# Secon2014_final_Schematic.net
KiCad netlist of a schematic drawn in EAGLE
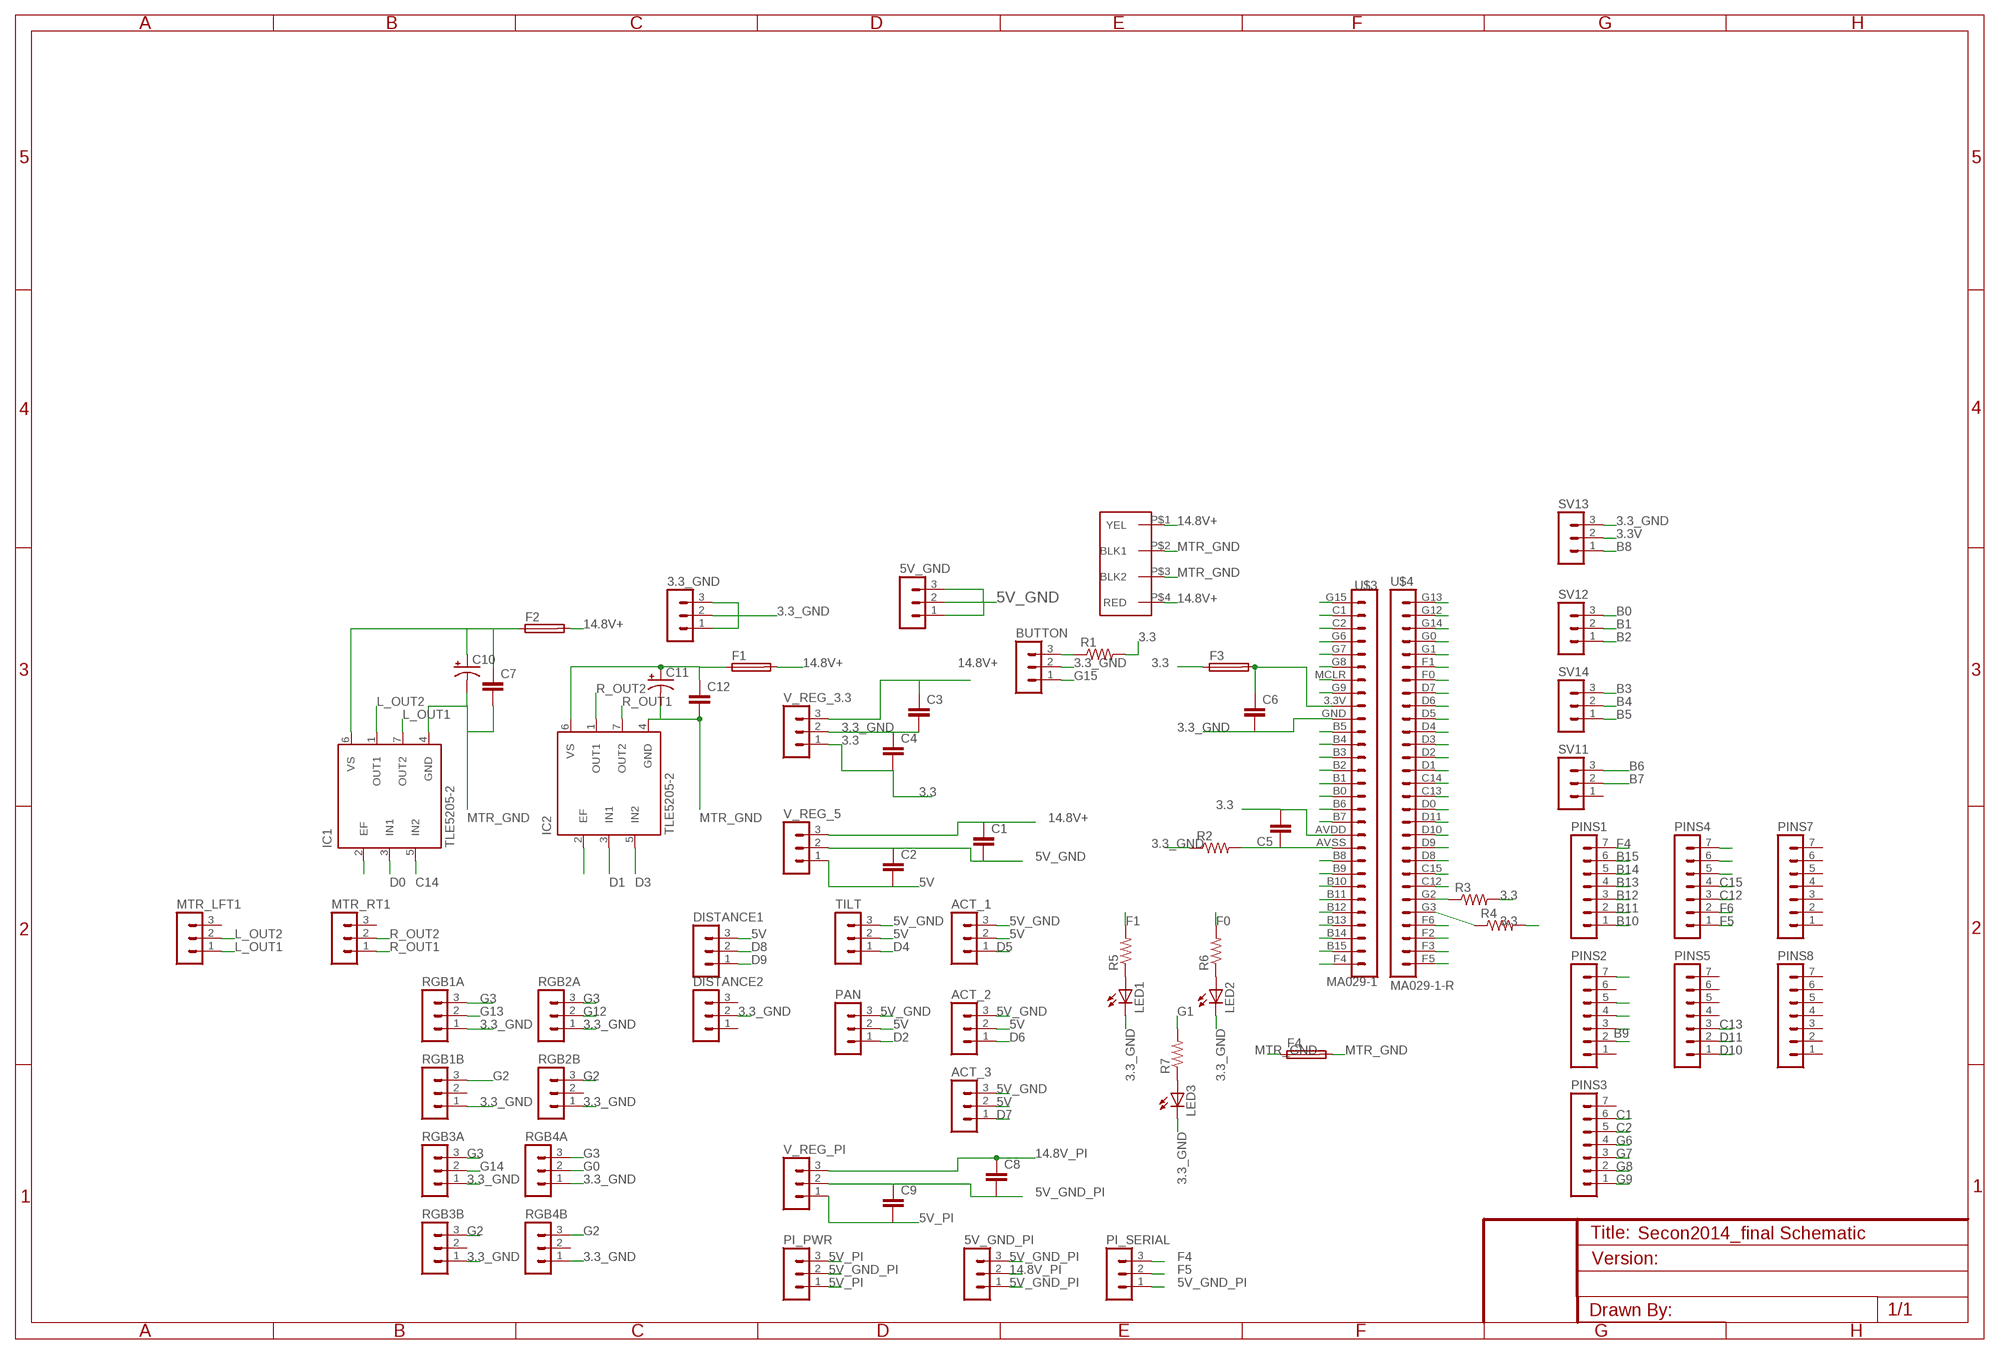
[diagram p0: schematic, sheet 1]

(export (version "E")
  (design (tool "Eeschema 10.0.6"))
  (components
    (comp (ref "3.3_GND")
      (value "MA03-1")
      (footprint "eagle-import:MA03-1")
      (libsource (lib "eagle-import") (part "MA03-1"))
    )
    (comp (ref "5V_GND")
      (value "MA03-1")
      (footprint "eagle-import:MA03-1")
      (libsource (lib "eagle-import") (part "MA03-1"))
    )
    (comp (ref "5V_GND_PI")
      (value "MA03-1")
      (footprint "eagle-import:MA03-1")
      (libsource (lib "eagle-import") (part "MA03-1"))
    )
    (comp (ref "ACT_1")
      (value "MA03-1")
      (footprint "eagle-import:MA03-1")
      (libsource (lib "eagle-import") (part "MA03-1"))
    )
    (comp (ref "ACT_2")
      (value "MA03-1")
      (footprint "eagle-import:MA03-1")
      (libsource (lib "eagle-import") (part "MA03-1"))
    )
    (comp (ref "ACT_3")
      (value "MA03-1")
      (footprint "eagle-import:MA03-1")
      (fields (field (name "OC_FARNELL") "unknown") (field (name "OC_NEWARK") "unknown"))
      (libsource (lib "eagle-import") (part "MA03-1"))
    )
    (comp (ref "BUTTON")
      (value "MA03-1")
      (footprint "eagle-import:MA03-1")
      (fields (field (name "OC_FARNELL") "unknown") (field (name "OC_NEWARK") "unknown"))
      (libsource (lib "eagle-import") (part "MA03-1"))
    )
    (comp (ref "C1")
      (value "CAPPTH2")
      (footprint "eagle-import:CAP-PTH-SMALL2")
      (libsource (lib "eagle-import") (part "CAPPTH2"))
    )
    (comp (ref "C2")
      (value "CAPPTH2")
      (footprint "eagle-import:CAP-PTH-SMALL2")
      (libsource (lib "eagle-import") (part "CAPPTH2"))
    )
    (comp (ref "C3")
      (value "CAPPTH2")
      (footprint "eagle-import:CAP-PTH-SMALL2")
      (libsource (lib "eagle-import") (part "CAPPTH2"))
    )
    (comp (ref "C4")
      (value "CAPPTH2")
      (footprint "eagle-import:CAP-PTH-SMALL2")
      (libsource (lib "eagle-import") (part "CAPPTH2"))
    )
    (comp (ref "C5")
      (value "CAPPTH2")
      (footprint "eagle-import:CAP-PTH-SMALL2")
      (libsource (lib "eagle-import") (part "CAPPTH2"))
    )
    (comp (ref "C6")
      (value "CAPPTH2")
      (footprint "eagle-import:CAP-PTH-SMALL2")
      (libsource (lib "eagle-import") (part "CAPPTH2"))
    )
    (comp (ref "C7")
      (value "CAPPTH2")
      (footprint "eagle-import:CAP-PTH-SMALL2")
      (libsource (lib "eagle-import") (part "CAPPTH2"))
    )
    (comp (ref "C8")
      (value "CAPPTH2")
      (footprint "eagle-import:CAP-PTH-SMALL2")
      (libsource (lib "eagle-import") (part "CAPPTH2"))
    )
    (comp (ref "C9")
      (value "CAPPTH2")
      (footprint "eagle-import:CAP-PTH-SMALL2")
      (libsource (lib "eagle-import") (part "CAPPTH2"))
    )
    (comp (ref "C10")
      (value "CAP_POLPTH1")
      (footprint "eagle-import:CPOL-RADIAL-100UF-25V")
      (libsource (lib "eagle-import") (part "CAP_POLPTH1"))
    )
    (comp (ref "C11")
      (value "CAP_POLPTH1")
      (footprint "eagle-import:CPOL-RADIAL-100UF-25V")
      (libsource (lib "eagle-import") (part "CAP_POLPTH1"))
    )
    (comp (ref "C12")
      (value "CAPPTH2")
      (footprint "eagle-import:CAP-PTH-SMALL2")
      (libsource (lib "eagle-import") (part "CAPPTH2"))
    )
    (comp (ref "DISTANCE1")
      (value "MA03-1")
      (footprint "eagle-import:MA03-1")
      (libsource (lib "eagle-import") (part "MA03-1"))
    )
    (comp (ref "DISTANCE2")
      (value "MA03-1")
      (footprint "eagle-import:MA03-1")
      (libsource (lib "eagle-import") (part "MA03-1"))
    )
    (comp (ref "F1")
      (value "TE5")
      (footprint "eagle-import:TE5")
      (libsource (lib "eagle-import") (part "TE5"))
    )
    (comp (ref "F2")
      (value "TE5")
      (footprint "eagle-import:TE5")
      (libsource (lib "eagle-import") (part "TE5"))
    )
    (comp (ref "F3")
      (value "TE5")
      (footprint "eagle-import:TE5")
      (libsource (lib "eagle-import") (part "TE5"))
    )
    (comp (ref "F4")
      (value "TE5")
      (footprint "eagle-import:TE5")
      (fields (field (name "OC_FARNELL") "unknown") (field (name "OC_NEWARK") "unknown"))
      (libsource (lib "eagle-import") (part "TE5"))
    )
    (comp (ref "IC1")
      (value "TLE5205-2")
      (footprint "eagle-import:P-TO220-7-11")
      (libsource (lib "eagle-import") (part "TLE5205-2"))
    )
    (comp (ref "IC2")
      (value "TLE5205-2")
      (footprint "eagle-import:P-TO220-7-11")
      (libsource (lib "eagle-import") (part "TLE5205-2"))
    )
    (comp (ref "LED1")
      (value "LED5MM")
      (footprint "eagle-import:LED5MM")
      (libsource (lib "eagle-import") (part "LED5MM"))
    )
    (comp (ref "LED2")
      (value "LED5MM")
      (footprint "eagle-import:LED5MM")
      (libsource (lib "eagle-import") (part "LED5MM"))
    )
    (comp (ref "LED3")
      (value "LED5MM")
      (footprint "eagle-import:LED5MM")
      (libsource (lib "eagle-import") (part "LED5MM"))
    )
    (comp (ref "MTR_LFT1")
      (value "MA03-1")
      (footprint "eagle-import:MA03-1")
      (libsource (lib "eagle-import") (part "MA03-1"))
    )
    (comp (ref "MTR_RT1")
      (value "MA03-1")
      (footprint "eagle-import:MA03-1")
      (libsource (lib "eagle-import") (part "MA03-1"))
    )
    (comp (ref "PAN")
      (value "MA03-1")
      (footprint "eagle-import:MA03-1")
      (libsource (lib "eagle-import") (part "MA03-1"))
    )
    (comp (ref "PINS1")
      (value "MA07-1")
      (footprint "eagle-import:MA07-1")
      (libsource (lib "eagle-import") (part "MA07-1"))
    )
    (comp (ref "PINS2")
      (value "MA07-1")
      (footprint "eagle-import:MA07-1")
      (libsource (lib "eagle-import") (part "MA07-1"))
    )
    (comp (ref "PINS3")
      (value "MA07-1")
      (footprint "eagle-import:MA07-1")
      (libsource (lib "eagle-import") (part "MA07-1"))
    )
    (comp (ref "PINS4")
      (value "MA07-1")
      (footprint "eagle-import:MA07-1")
      (libsource (lib "eagle-import") (part "MA07-1"))
    )
    (comp (ref "PINS5")
      (value "MA07-1")
      (footprint "eagle-import:MA07-1")
      (libsource (lib "eagle-import") (part "MA07-1"))
    )
    (comp (ref "PINS7")
      (value "MA07-1")
      (footprint "eagle-import:MA07-1")
      (libsource (lib "eagle-import") (part "MA07-1"))
    )
    (comp (ref "PINS8")
      (value "MA07-1")
      (footprint "eagle-import:MA07-1")
      (libsource (lib "eagle-import") (part "MA07-1"))
    )
    (comp (ref "PI_PWR")
      (value "MA03-1")
      (footprint "eagle-import:MA03-1")
      (libsource (lib "eagle-import") (part "MA03-1"))
    )
    (comp (ref "PI_SERIAL")
      (value "MA03-1")
      (footprint "eagle-import:MA03-1")
      (fields (field (name "OC_FARNELL") "unknown") (field (name "OC_NEWARK") "unknown"))
      (libsource (lib "eagle-import") (part "MA03-1"))
    )
    (comp (ref "R1")
      (value "RESISTORPTH-1/4W")
      (footprint "eagle-import:AXIAL-0.4")
      (libsource (lib "eagle-import") (part "RESISTORPTH-1/4W"))
    )
    (comp (ref "R2")
      (value "RESISTORPTH-1/4W")
      (footprint "eagle-import:AXIAL-0.4")
      (libsource (lib "eagle-import") (part "RESISTORPTH-1/4W"))
    )
    (comp (ref "R3")
      (value "RESISTORPTH-1/4W")
      (footprint "eagle-import:AXIAL-0.4")
      (libsource (lib "eagle-import") (part "RESISTORPTH-1/4W"))
    )
    (comp (ref "R4")
      (value "RESISTORPTH-1/4W")
      (footprint "eagle-import:AXIAL-0.4")
      (libsource (lib "eagle-import") (part "RESISTORPTH-1/4W"))
    )
    (comp (ref "R5")
      (value "RESISTORPTH-1/4W")
      (footprint "eagle-import:AXIAL-0.4")
      (libsource (lib "eagle-import") (part "RESISTORPTH-1/4W"))
    )
    (comp (ref "R6")
      (value "RESISTORPTH-1/4W")
      (footprint "eagle-import:AXIAL-0.4")
      (libsource (lib "eagle-import") (part "RESISTORPTH-1/4W"))
    )
    (comp (ref "R7")
      (value "RESISTORPTH-1/4W")
      (footprint "eagle-import:AXIAL-0.4")
      (libsource (lib "eagle-import") (part "RESISTORPTH-1/4W"))
    )
    (comp (ref "RGB1A")
      (value "MA03-1")
      (footprint "eagle-import:MA03-1")
      (libsource (lib "eagle-import") (part "MA03-1"))
    )
    (comp (ref "RGB1B")
      (value "MA03-1")
      (footprint "eagle-import:MA03-1")
      (libsource (lib "eagle-import") (part "MA03-1"))
    )
    (comp (ref "RGB2A")
      (value "MA03-1")
      (footprint "eagle-import:MA03-1")
      (libsource (lib "eagle-import") (part "MA03-1"))
    )
    (comp (ref "RGB2B")
      (value "MA03-1")
      (footprint "eagle-import:MA03-1")
      (libsource (lib "eagle-import") (part "MA03-1"))
    )
    (comp (ref "RGB3A")
      (value "MA03-1")
      (footprint "eagle-import:MA03-1")
      (libsource (lib "eagle-import") (part "MA03-1"))
    )
    (comp (ref "RGB3B")
      (value "MA03-1")
      (footprint "eagle-import:MA03-1")
      (libsource (lib "eagle-import") (part "MA03-1"))
    )
    (comp (ref "RGB4A")
      (value "MA03-1")
      (footprint "eagle-import:MA03-1")
      (libsource (lib "eagle-import") (part "MA03-1"))
    )
    (comp (ref "RGB4B")
      (value "MA03-1")
      (footprint "eagle-import:MA03-1")
      (libsource (lib "eagle-import") (part "MA03-1"))
    )
    (comp (ref "SV11")
      (value "MA03-1")
      (footprint "eagle-import:MA03-1")
      (libsource (lib "eagle-import") (part "MA03-1"))
    )
    (comp (ref "SV12")
      (value "MA03-1")
      (footprint "eagle-import:MA03-1")
      (libsource (lib "eagle-import") (part "MA03-1"))
    )
    (comp (ref "SV13")
      (value "MA03-1")
      (footprint "eagle-import:MA03-1")
      (libsource (lib "eagle-import") (part "MA03-1"))
    )
    (comp (ref "SV14")
      (value "MA03-1")
      (footprint "eagle-import:MA03-1")
      (libsource (lib "eagle-import") (part "MA03-1"))
    )
    (comp (ref "TILT")
      (value "MA03-1")
      (footprint "eagle-import:MA03-1")
      (libsource (lib "eagle-import") (part "MA03-1"))
    )
    (comp (ref "U$1")
      (value "MOLEX-4PINPWR")
      (footprint "eagle-import:MOLEX_4PWR")
      (libsource (lib "eagle-import") (part "MOLEX-4PINPWR"))
    )
    (comp (ref "U$3")
      (value "MA029-1")
      (footprint "eagle-import:MA029-1")
      (libsource (lib "eagle-import") (part "MA029-1"))
    )
    (comp (ref "U$4")
      (value "MA029-1-R")
      (footprint "eagle-import:MA029-1-R")
      (libsource (lib "eagle-import") (part "MA029-1-R"))
    )
    (comp (ref "V_REG_3.3")
      (value "MA03-1")
      (footprint "eagle-import:MA03-1")
      (libsource (lib "eagle-import") (part "MA03-1"))
    )
    (comp (ref "V_REG_5")
      (value "MA03-1")
      (footprint "eagle-import:MA03-1")
      (libsource (lib "eagle-import") (part "MA03-1"))
    )
    (comp (ref "V_REG_PI")
      (value "MA03-1")
      (footprint "eagle-import:MA03-1")
      (libsource (lib "eagle-import") (part "MA03-1"))
    )
  )
  (nets
    (net (code "1") (name "/3.3") (class "Default")
      (node (ref "C4") (pin "2") (pinfunction "2_2") (pintype "passive"))
      (node (ref "C5") (pin "2") (pinfunction "2_2") (pintype "passive"))
      (node (ref "F3") (pin "1") (pinfunction "1_1") (pintype "passive"))
      (node (ref "R1") (pin "P$2") (pinfunction "2_P$2") (pintype "passive"))
      (node (ref "R3") (pin "P$2") (pinfunction "2_P$2") (pintype "passive"))
      (node (ref "R4") (pin "P$2") (pinfunction "2_P$2") (pintype "passive"))
      (node (ref "U$3") (pin "AVDD") (pinfunction "19_AVDD") (pintype "passive"))
      (node (ref "V_REG_3.3") (pin "1") (pinfunction "1_1") (pintype "passive"))
    )
    (net (code "2") (name "/3.3V") (class "Default")
      (node (ref "SV13") (pin "2") (pinfunction "2_2") (pintype "passive"))
    )
    (net (code "3") (name "/3.3_GND") (class "Default")
      (node (ref "3.3_GND") (pin "1") (pinfunction "1_1") (pintype "passive"))
      (node (ref "3.3_GND") (pin "2") (pinfunction "2_2") (pintype "passive"))
      (node (ref "3.3_GND") (pin "3") (pinfunction "3_3") (pintype "passive"))
      (node (ref "BUTTON") (pin "2") (pinfunction "2_2") (pintype "passive"))
      (node (ref "C3") (pin "2") (pinfunction "2_2") (pintype "passive"))
      (node (ref "C4") (pin "1") (pinfunction "1_1") (pintype "passive"))
      (node (ref "C6") (pin "2") (pinfunction "2_2") (pintype "passive"))
      (node (ref "DISTANCE2") (pin "2") (pinfunction "2_2") (pintype "passive"))
      (node (ref "LED1") (pin "K") (pinfunction "C_K") (pintype "passive"))
      (node (ref "LED2") (pin "K") (pinfunction "C_K") (pintype "passive"))
      (node (ref "LED3") (pin "K") (pinfunction "C_K") (pintype "passive"))
      (node (ref "R2") (pin "P$1") (pinfunction "1_P$1") (pintype "passive"))
      (node (ref "RGB1A") (pin "1") (pinfunction "1_1") (pintype "passive"))
      (node (ref "RGB1B") (pin "1") (pinfunction "1_1") (pintype "passive"))
      (node (ref "RGB2A") (pin "1") (pinfunction "1_1") (pintype "passive"))
      (node (ref "RGB2B") (pin "1") (pinfunction "1_1") (pintype "passive"))
      (node (ref "RGB3A") (pin "1") (pinfunction "1_1") (pintype "passive"))
      (node (ref "RGB3B") (pin "1") (pinfunction "1_1") (pintype "passive"))
      (node (ref "RGB4A") (pin "1") (pinfunction "1_1") (pintype "passive"))
      (node (ref "RGB4B") (pin "1") (pinfunction "1_1") (pintype "passive"))
      (node (ref "SV13") (pin "3") (pinfunction "3_3") (pintype "passive"))
      (node (ref "U$3") (pin "GND") (pinfunction "10_GND") (pintype "passive"))
      (node (ref "V_REG_3.3") (pin "2") (pinfunction "2_2") (pintype "passive"))
    )
    (net (code "4") (name "/5V") (class "Default")
      (node (ref "ACT_1") (pin "2") (pinfunction "2_2") (pintype "passive"))
      (node (ref "ACT_2") (pin "2") (pinfunction "2_2") (pintype "passive"))
      (node (ref "ACT_3") (pin "2") (pinfunction "2_2") (pintype "passive"))
      (node (ref "C2") (pin "2") (pinfunction "2_2") (pintype "passive"))
      (node (ref "DISTANCE1") (pin "3") (pinfunction "3_3") (pintype "passive"))
      (node (ref "PAN") (pin "2") (pinfunction "2_2") (pintype "passive"))
      (node (ref "TILT") (pin "2") (pinfunction "2_2") (pintype "passive"))
      (node (ref "V_REG_5") (pin "1") (pinfunction "1_1") (pintype "passive"))
    )
    (net (code "5") (name "/5V_GND") (class "Default")
      (node (ref "5V_GND") (pin "1") (pinfunction "1_1") (pintype "passive"))
      (node (ref "5V_GND") (pin "2") (pinfunction "2_2") (pintype "passive"))
      (node (ref "5V_GND") (pin "3") (pinfunction "3_3") (pintype "passive"))
      (node (ref "ACT_1") (pin "3") (pinfunction "3_3") (pintype "passive"))
      (node (ref "ACT_2") (pin "3") (pinfunction "3_3") (pintype "passive"))
      (node (ref "ACT_3") (pin "3") (pinfunction "3_3") (pintype "passive"))
      (node (ref "C1") (pin "2") (pinfunction "2_2") (pintype "passive"))
      (node (ref "C2") (pin "1") (pinfunction "1_1") (pintype "passive"))
      (node (ref "PAN") (pin "3") (pinfunction "3_3") (pintype "passive"))
      (node (ref "TILT") (pin "3") (pinfunction "3_3") (pintype "passive"))
      (node (ref "V_REG_5") (pin "2") (pinfunction "2_2") (pintype "passive"))
    )
    (net (code "6") (name "/5V_GND_PI") (class "Default")
      (node (ref "5V_GND_PI") (pin "1") (pinfunction "1_1") (pintype "passive"))
      (node (ref "5V_GND_PI") (pin "3") (pinfunction "3_3") (pintype "passive"))
      (node (ref "C8") (pin "2") (pinfunction "2_2") (pintype "passive"))
      (node (ref "C9") (pin "1") (pinfunction "1_1") (pintype "passive"))
      (node (ref "PI_PWR") (pin "2") (pinfunction "2_2") (pintype "passive"))
      (node (ref "PI_SERIAL") (pin "1") (pinfunction "1_1") (pintype "passive"))
      (node (ref "V_REG_PI") (pin "2") (pinfunction "2_2") (pintype "passive"))
    )
    (net (code "7") (name "/5V_PI") (class "Default")
      (node (ref "C9") (pin "2") (pinfunction "2_2") (pintype "passive"))
      (node (ref "PI_PWR") (pin "1") (pinfunction "1_1") (pintype "passive"))
      (node (ref "PI_PWR") (pin "3") (pinfunction "3_3") (pintype "passive"))
      (node (ref "V_REG_PI") (pin "1") (pinfunction "1_1") (pintype "passive"))
    )
    (net (code "8") (name "/14.8V+") (class "Default")
      (node (ref "C1") (pin "1") (pinfunction "1_1") (pintype "passive"))
      (node (ref "C3") (pin "1") (pinfunction "1_1") (pintype "passive"))
      (node (ref "F1") (pin "2") (pinfunction "2_2") (pintype "passive"))
      (node (ref "F2") (pin "2") (pinfunction "2_2") (pintype "passive"))
      (node (ref "U$1") (pin "P$1") (pinfunction "YEL_P$1") (pintype "bidirectional"))
      (node (ref "U$1") (pin "P$4") (pinfunction "RED_P$4") (pintype "bidirectional"))
      (node (ref "V_REG_3.3") (pin "3") (pinfunction "3_3") (pintype "passive"))
      (node (ref "V_REG_5") (pin "3") (pinfunction "3_3") (pintype "passive"))
    )
    (net (code "9") (name "/14.8V_PI") (class "Default")
      (node (ref "5V_GND_PI") (pin "2") (pinfunction "2_2") (pintype "passive"))
      (node (ref "C8") (pin "1") (pinfunction "1_1") (pintype "passive"))
      (node (ref "V_REG_PI") (pin "3") (pinfunction "3_3") (pintype "passive"))
    )
    (net (code "10") (name "/B0") (class "Default")
      (node (ref "SV12") (pin "3") (pinfunction "3_3") (pintype "passive"))
      (node (ref "U$3") (pin "B0") (pinfunction "16_B0") (pintype "passive"))
    )
    (net (code "11") (name "/B1") (class "Default")
      (node (ref "SV12") (pin "2") (pinfunction "2_2") (pintype "passive"))
      (node (ref "U$3") (pin "B1") (pinfunction "15_B1") (pintype "passive"))
    )
    (net (code "12") (name "/B2") (class "Default")
      (node (ref "SV12") (pin "1") (pinfunction "1_1") (pintype "passive"))
      (node (ref "U$3") (pin "B2") (pinfunction "14_B2") (pintype "passive"))
    )
    (net (code "13") (name "/B3") (class "Default")
      (node (ref "SV14") (pin "3") (pinfunction "3_3") (pintype "passive"))
      (node (ref "U$3") (pin "B3") (pinfunction "13_B3") (pintype "passive"))
    )
    (net (code "14") (name "/B4") (class "Default")
      (node (ref "SV14") (pin "2") (pinfunction "2_2") (pintype "passive"))
      (node (ref "U$3") (pin "B4") (pinfunction "12_B4") (pintype "passive"))
    )
    (net (code "15") (name "/B5") (class "Default")
      (node (ref "SV14") (pin "1") (pinfunction "1_1") (pintype "passive"))
      (node (ref "U$3") (pin "B5") (pinfunction "11_B5") (pintype "passive"))
    )
    (net (code "16") (name "/B6") (class "Default")
      (node (ref "SV11") (pin "3") (pinfunction "3_3") (pintype "passive"))
      (node (ref "U$3") (pin "B6") (pinfunction "17_B6") (pintype "passive"))
    )
    (net (code "17") (name "/B7") (class "Default")
      (node (ref "SV11") (pin "2") (pinfunction "2_2") (pintype "passive"))
      (node (ref "U$3") (pin "B7") (pinfunction "18_B7") (pintype "passive"))
    )
    (net (code "18") (name "/B8") (class "Default")
      (node (ref "SV13") (pin "1") (pinfunction "1_1") (pintype "passive"))
      (node (ref "U$3") (pin "B8") (pinfunction "21_B8") (pintype "passive"))
    )
    (net (code "19") (name "/B9") (class "Default")
      (node (ref "PINS2") (pin "2") (pinfunction "2_2") (pintype "passive"))
      (node (ref "U$3") (pin "B9") (pinfunction "22_B9") (pintype "passive"))
    )
    (net (code "20") (name "/B10") (class "Default")
      (node (ref "PINS1") (pin "1") (pinfunction "1_1") (pintype "passive"))
      (node (ref "U$3") (pin "B10") (pinfunction "23_B10") (pintype "passive"))
    )
    (net (code "21") (name "/B11") (class "Default")
      (node (ref "PINS1") (pin "2") (pinfunction "2_2") (pintype "passive"))
      (node (ref "U$3") (pin "B11") (pinfunction "24_B11") (pintype "passive"))
    )
    (net (code "22") (name "/B12") (class "Default")
      (node (ref "PINS1") (pin "3") (pinfunction "3_3") (pintype "passive"))
      (node (ref "U$3") (pin "B12") (pinfunction "25_B12") (pintype "passive"))
    )
    (net (code "23") (name "/B13") (class "Default")
      (node (ref "PINS1") (pin "4") (pinfunction "4_4") (pintype "passive"))
      (node (ref "U$3") (pin "B13") (pinfunction "26_B13") (pintype "passive"))
    )
    (net (code "24") (name "/B14") (class "Default")
      (node (ref "PINS1") (pin "5") (pinfunction "5_5") (pintype "passive"))
      (node (ref "U$3") (pin "B14") (pinfunction "27_B14") (pintype "passive"))
    )
    (net (code "25") (name "/B15") (class "Default")
      (node (ref "PINS1") (pin "6") (pinfunction "6_6") (pintype "passive"))
      (node (ref "U$3") (pin "B15") (pinfunction "28_B15") (pintype "passive"))
    )
    (net (code "26") (name "/C1") (class "Default")
      (node (ref "PINS3") (pin "6") (pinfunction "6_6") (pintype "passive"))
      (node (ref "U$3") (pin "C1") (pinfunction "2_C1") (pintype "passive"))
    )
    (net (code "27") (name "/C2") (class "Default")
      (node (ref "PINS3") (pin "5") (pinfunction "5_5") (pintype "passive"))
      (node (ref "U$3") (pin "C2") (pinfunction "3_C2") (pintype "passive"))
    )
    (net (code "28") (name "/C12") (class "Default")
      (node (ref "PINS4") (pin "3") (pinfunction "3_3") (pintype "passive"))
      (node (ref "U$4") (pin "C12") (pinfunction "C12_C12") (pintype "passive"))
    )
    (net (code "29") (name "/C13") (class "Default")
      (node (ref "PINS5") (pin "3") (pinfunction "3_3") (pintype "passive"))
      (node (ref "U$4") (pin "C13") (pinfunction "C13_C13") (pintype "passive"))
    )
    (net (code "30") (name "/C14") (class "Default")
      (node (ref "IC1") (pin "5") (pinfunction "IN2_5") (pintype "input"))
      (node (ref "U$4") (pin "C14") (pinfunction "C14_C14") (pintype "passive"))
    )
    (net (code "31") (name "/C15") (class "Default")
      (node (ref "PINS4") (pin "4") (pinfunction "4_4") (pintype "passive"))
      (node (ref "U$4") (pin "C15") (pinfunction "C15_C15") (pintype "passive"))
    )
    (net (code "32") (name "/D0") (class "Default")
      (node (ref "IC1") (pin "3") (pinfunction "IN1_3") (pintype "input"))
      (node (ref "U$4") (pin "D0") (pinfunction "D0_D0") (pintype "passive"))
    )
    (net (code "33") (name "/D1") (class "Default")
      (node (ref "IC2") (pin "3") (pinfunction "IN1_3") (pintype "input"))
      (node (ref "U$4") (pin "D1") (pinfunction "D1_D1") (pintype "passive"))
    )
    (net (code "34") (name "/D2") (class "Default")
      (node (ref "PAN") (pin "1") (pinfunction "1_1") (pintype "passive"))
      (node (ref "U$4") (pin "D2") (pinfunction "D2_D2") (pintype "passive"))
    )
    (net (code "35") (name "/D3") (class "Default")
      (node (ref "IC2") (pin "5") (pinfunction "IN2_5") (pintype "input"))
      (node (ref "U$4") (pin "D3") (pinfunction "D3_D3") (pintype "passive"))
    )
    (net (code "36") (name "/D4") (class "Default")
      (node (ref "TILT") (pin "1") (pinfunction "1_1") (pintype "passive"))
      (node (ref "U$4") (pin "D4") (pinfunction "D4_D4") (pintype "passive"))
    )
    (net (code "37") (name "/D5") (class "Default")
      (node (ref "ACT_1") (pin "1") (pinfunction "1_1") (pintype "passive"))
      (node (ref "U$4") (pin "D5") (pinfunction "D5_D5") (pintype "passive"))
    )
    (net (code "38") (name "/D6") (class "Default")
      (node (ref "ACT_2") (pin "1") (pinfunction "1_1") (pintype "passive"))
      (node (ref "U$4") (pin "D6") (pinfunction "D6_D6") (pintype "passive"))
    )
    (net (code "39") (name "/D7") (class "Default")
      (node (ref "ACT_3") (pin "1") (pinfunction "1_1") (pintype "passive"))
      (node (ref "U$4") (pin "D7") (pinfunction "D7_D7") (pintype "passive"))
    )
    (net (code "40") (name "/D8") (class "Default")
      (node (ref "DISTANCE1") (pin "2") (pinfunction "2_2") (pintype "passive"))
      (node (ref "U$4") (pin "D8") (pinfunction "D8_D8") (pintype "passive"))
    )
    (net (code "41") (name "/D9") (class "Default")
      (node (ref "DISTANCE1") (pin "1") (pinfunction "1_1") (pintype "passive"))
      (node (ref "U$4") (pin "D9") (pinfunction "D9_D9") (pintype "passive"))
    )
    (net (code "42") (name "/D10") (class "Default")
      (node (ref "PINS5") (pin "1") (pinfunction "1_1") (pintype "passive"))
      (node (ref "U$4") (pin "D10") (pinfunction "D10_D10") (pintype "passive"))
    )
    (net (code "43") (name "/D11") (class "Default")
      (node (ref "PINS5") (pin "2") (pinfunction "2_2") (pintype "passive"))
      (node (ref "U$4") (pin "D11") (pinfunction "D11_D11") (pintype "passive"))
    )
    (net (code "44") (name "/F0") (class "Default")
      (node (ref "R6") (pin "P$2") (pinfunction "2_P$2") (pintype "passive"))
      (node (ref "U$4") (pin "F0") (pinfunction "F0_F0") (pintype "passive"))
    )
    (net (code "45") (name "/F1") (class "Default")
      (node (ref "R5") (pin "P$2") (pinfunction "2_P$2") (pintype "passive"))
      (node (ref "U$4") (pin "F1") (pinfunction "F1_F1") (pintype "passive"))
    )
    (net (code "46") (name "/F4") (class "Default")
      (node (ref "PINS1") (pin "7") (pinfunction "7_7") (pintype "passive"))
      (node (ref "PI_SERIAL") (pin "3") (pinfunction "3_3") (pintype "passive"))
      (node (ref "U$3") (pin "F4") (pinfunction "29_F4") (pintype "passive"))
    )
    (net (code "47") (name "/F5") (class "Default")
      (node (ref "PINS4") (pin "1") (pinfunction "1_1") (pintype "passive"))
      (node (ref "PI_SERIAL") (pin "2") (pinfunction "2_2") (pintype "passive"))
      (node (ref "U$4") (pin "F5") (pinfunction "F5_F5") (pintype "passive"))
    )
    (net (code "48") (name "/F6") (class "Default")
      (node (ref "PINS4") (pin "2") (pinfunction "2_2") (pintype "passive"))
      (node (ref "U$4") (pin "F6") (pinfunction "F6_F6") (pintype "passive"))
    )
    (net (code "49") (name "/G0") (class "Default")
      (node (ref "RGB4A") (pin "2") (pinfunction "2_2") (pintype "passive"))
      (node (ref "U$4") (pin "G0") (pinfunction "G0_G0") (pintype "passive"))
    )
    (net (code "50") (name "/G1") (class "Default")
      (node (ref "R7") (pin "P$2") (pinfunction "2_P$2") (pintype "passive"))
      (node (ref "U$4") (pin "G1") (pinfunction "G1_G1") (pintype "passive"))
    )
    (net (code "51") (name "/G2") (class "Default")
      (node (ref "RGB1B") (pin "3") (pinfunction "3_3") (pintype "passive"))
      (node (ref "RGB2B") (pin "3") (pinfunction "3_3") (pintype "passive"))
      (node (ref "RGB3B") (pin "3") (pinfunction "3_3") (pintype "passive"))
      (node (ref "RGB4B") (pin "3") (pinfunction "3_3") (pintype "passive"))
    )
    (net (code "52") (name "/G3") (class "Default")
      (node (ref "RGB1A") (pin "3") (pinfunction "3_3") (pintype "passive"))
      (node (ref "RGB2A") (pin "3") (pinfunction "3_3") (pintype "passive"))
      (node (ref "RGB3A") (pin "3") (pinfunction "3_3") (pintype "passive"))
      (node (ref "RGB4A") (pin "3") (pinfunction "3_3") (pintype "passive"))
    )
    (net (code "53") (name "/G6") (class "Default")
      (node (ref "PINS3") (pin "4") (pinfunction "4_4") (pintype "passive"))
      (node (ref "U$3") (pin "G6") (pinfunction "4_G6") (pintype "passive"))
    )
    (net (code "54") (name "/G7") (class "Default")
      (node (ref "PINS3") (pin "3") (pinfunction "3_3") (pintype "passive"))
      (node (ref "U$3") (pin "G7") (pinfunction "5_G7") (pintype "passive"))
    )
    (net (code "55") (name "/G8") (class "Default")
      (node (ref "PINS3") (pin "2") (pinfunction "2_2") (pintype "passive"))
      (node (ref "U$3") (pin "G8") (pinfunction "6_G8") (pintype "passive"))
    )
    (net (code "56") (name "/G9") (class "Default")
      (node (ref "PINS3") (pin "1") (pinfunction "1_1") (pintype "passive"))
      (node (ref "U$3") (pin "G9") (pinfunction "8_G9") (pintype "passive"))
    )
    (net (code "57") (name "/G12") (class "Default")
      (node (ref "RGB2A") (pin "2") (pinfunction "2_2") (pintype "passive"))
      (node (ref "U$4") (pin "G12") (pinfunction "G12_G12") (pintype "passive"))
    )
    (net (code "58") (name "/G13") (class "Default")
      (node (ref "RGB1A") (pin "2") (pinfunction "2_2") (pintype "passive"))
      (node (ref "U$4") (pin "G13") (pinfunction "G13_G13") (pintype "passive"))
    )
    (net (code "59") (name "/G14") (class "Default")
      (node (ref "RGB3A") (pin "2") (pinfunction "2_2") (pintype "passive"))
      (node (ref "U$4") (pin "G14") (pinfunction "G14_G14") (pintype "passive"))
    )
    (net (code "60") (name "/G15") (class "Default")
      (node (ref "BUTTON") (pin "1") (pinfunction "1_1") (pintype "passive"))
      (node (ref "U$3") (pin "G15") (pinfunction "1_G15") (pintype "passive"))
    )
    (net (code "61") (name "/L_OUT1") (class "Default")
      (node (ref "IC1") (pin "7") (pinfunction "OUT2_7") (pintype "output"))
      (node (ref "MTR_LFT1") (pin "1") (pinfunction "1_1") (pintype "passive"))
    )
    (net (code "62") (name "/L_OUT2") (class "Default")
      (node (ref "IC1") (pin "1") (pinfunction "OUT1_1") (pintype "output"))
      (node (ref "MTR_LFT1") (pin "2") (pinfunction "2_2") (pintype "passive"))
    )
    (net (code "63") (name "/MTR_GND") (class "Default")
      (node (ref "C10") (pin "2") (pinfunction "-_2") (pintype "passive"))
      (node (ref "C11") (pin "2") (pinfunction "-_2") (pintype "passive"))
      (node (ref "C12") (pin "2") (pinfunction "2_2") (pintype "passive"))
      (node (ref "C7") (pin "2") (pinfunction "2_2") (pintype "passive"))
      (node (ref "F4") (pin "1") (pinfunction "1_1") (pintype "passive"))
      (node (ref "F4") (pin "2") (pinfunction "2_2") (pintype "passive"))
      (node (ref "IC1") (pin "4") (pinfunction "GND_4") (pintype "power_in"))
      (node (ref "IC2") (pin "4") (pinfunction "GND_4") (pintype "power_in"))
      (node (ref "U$1") (pin "P$2") (pinfunction "BLK1_P$2") (pintype "bidirectional"))
      (node (ref "U$1") (pin "P$3") (pinfunction "BLK2_P$3") (pintype "bidirectional"))
    )
    (net (code "64") (name "/R_OUT1") (class "Default")
      (node (ref "IC2") (pin "7") (pinfunction "OUT2_7") (pintype "output"))
      (node (ref "MTR_RT1") (pin "1") (pinfunction "1_1") (pintype "passive"))
    )
    (net (code "65") (name "/R_OUT2") (class "Default")
      (node (ref "IC2") (pin "1") (pinfunction "OUT1_1") (pintype "output"))
      (node (ref "MTR_RT1") (pin "2") (pinfunction "2_2") (pintype "passive"))
    )
    (net (code "66") (name "Net-(C10-+)") (class "Default")
      (node (ref "C10") (pin "1") (pinfunction "+_1") (pintype "passive"))
      (node (ref "C7") (pin "1") (pinfunction "1_1") (pintype "passive"))
      (node (ref "F2") (pin "1") (pinfunction "1_1") (pintype "passive"))
      (node (ref "IC1") (pin "6") (pinfunction "VS_6") (pintype "input"))
    )
    (net (code "67") (name "Net-(C11-+)") (class "Default")
      (node (ref "C11") (pin "1") (pinfunction "+_1") (pintype "passive"))
      (node (ref "C12") (pin "1") (pinfunction "1_1") (pintype "passive"))
      (node (ref "F1") (pin "1") (pinfunction "1_1") (pintype "passive"))
      (node (ref "IC2") (pin "6") (pinfunction "VS_6") (pintype "input"))
    )
    (net (code "68") (name "Net-(R1-1)") (class "Default")
      (node (ref "BUTTON") (pin "3") (pinfunction "3_3") (pintype "passive"))
      (node (ref "R1") (pin "P$1") (pinfunction "1_P$1") (pintype "passive"))
    )
    (net (code "69") (name "Net-(R2-2)") (class "Default")
      (node (ref "C5") (pin "1") (pinfunction "1_1") (pintype "passive"))
      (node (ref "R2") (pin "P$2") (pinfunction "2_P$2") (pintype "passive"))
      (node (ref "U$3") (pin "AVSS") (pinfunction "20_AVSS") (pintype "passive"))
    )
    (net (code "70") (name "Net-(R3-1)") (class "Default")
      (node (ref "R3") (pin "P$1") (pinfunction "1_P$1") (pintype "passive"))
      (node (ref "U$4") (pin "G2") (pinfunction "G2_G2") (pintype "passive"))
    )
    (net (code "71") (name "Net-(R4-1)") (class "Default")
      (node (ref "R4") (pin "P$1") (pinfunction "1_P$1") (pintype "passive"))
      (node (ref "U$4") (pin "G3") (pinfunction "G3_G3") (pintype "passive"))
    )
    (net (code "72") (name "Net-(R5-1)") (class "Default")
      (node (ref "LED1") (pin "A") (pinfunction "A_A") (pintype "passive"))
      (node (ref "R5") (pin "P$1") (pinfunction "1_P$1") (pintype "passive"))
    )
    (net (code "73") (name "Net-(R6-1)") (class "Default")
      (node (ref "LED2") (pin "A") (pinfunction "A_A") (pintype "passive"))
      (node (ref "R6") (pin "P$1") (pinfunction "1_P$1") (pintype "passive"))
    )
    (net (code "74") (name "Net-(R7-1)") (class "Default")
      (node (ref "LED3") (pin "A") (pinfunction "A_A") (pintype "passive"))
      (node (ref "R7") (pin "P$1") (pinfunction "1_P$1") (pintype "passive"))
    )
    (net (code "75") (name "Net-(U$3-9)") (class "Default")
      (node (ref "C6") (pin "1") (pinfunction "1_1") (pintype "passive"))
      (node (ref "F3") (pin "2") (pinfunction "2_2") (pintype "passive"))
      (node (ref "U$3") (pin "3.3V") (pinfunction "9_3.3V") (pintype "passive"))
    )
    (net (code "76") (name "unconnected-(DISTANCE2-Pad1)") (class "Default")
      (node (ref "DISTANCE2") (pin "1") (pinfunction "1_1") (pintype "passive"))
    )
    (net (code "77") (name "unconnected-(DISTANCE2-Pad3)") (class "Default")
      (node (ref "DISTANCE2") (pin "3") (pinfunction "3_3") (pintype "passive"))
    )
    (net (code "78") (name "unconnected-(IC1-EF-Pad2)") (class "Default")
      (node (ref "IC1") (pin "2") (pinfunction "EF_2") (pintype "open_collector"))
    )
    (net (code "79") (name "unconnected-(IC2-EF-Pad2)") (class "Default")
      (node (ref "IC2") (pin "2") (pinfunction "EF_2") (pintype "open_collector"))
    )
    (net (code "80") (name "unconnected-(MTR_LFT1-Pad3)") (class "Default")
      (node (ref "MTR_LFT1") (pin "3") (pinfunction "3_3") (pintype "passive"))
    )
    (net (code "81") (name "unconnected-(MTR_RT1-Pad3)") (class "Default")
      (node (ref "MTR_RT1") (pin "3") (pinfunction "3_3") (pintype "passive"))
    )
    (net (code "82") (name "unconnected-(PINS2-Pad1)") (class "Default")
      (node (ref "PINS2") (pin "1") (pinfunction "1_1") (pintype "passive"))
    )
    (net (code "83") (name "unconnected-(PINS2-Pad3)") (class "Default")
      (node (ref "PINS2") (pin "3") (pinfunction "3_3") (pintype "passive"))
    )
    (net (code "84") (name "unconnected-(PINS2-Pad4)") (class "Default")
      (node (ref "PINS2") (pin "4") (pinfunction "4_4") (pintype "passive"))
    )
    (net (code "85") (name "unconnected-(PINS2-Pad5)") (class "Default")
      (node (ref "PINS2") (pin "5") (pinfunction "5_5") (pintype "passive"))
    )
    (net (code "86") (name "unconnected-(PINS2-Pad6)") (class "Default")
      (node (ref "PINS2") (pin "6") (pinfunction "6_6") (pintype "passive"))
    )
    (net (code "87") (name "unconnected-(PINS2-Pad7)") (class "Default")
      (node (ref "PINS2") (pin "7") (pinfunction "7_7") (pintype "passive"))
    )
    (net (code "88") (name "unconnected-(PINS3-Pad7)") (class "Default")
      (node (ref "PINS3") (pin "7") (pinfunction "7_7") (pintype "passive"))
    )
    (net (code "89") (name "unconnected-(PINS4-Pad5)") (class "Default")
      (node (ref "PINS4") (pin "5") (pinfunction "5_5") (pintype "passive"))
    )
    (net (code "90") (name "unconnected-(PINS4-Pad6)") (class "Default")
      (node (ref "PINS4") (pin "6") (pinfunction "6_6") (pintype "passive"))
    )
    (net (code "91") (name "unconnected-(PINS4-Pad7)") (class "Default")
      (node (ref "PINS4") (pin "7") (pinfunction "7_7") (pintype "passive"))
    )
    (net (code "92") (name "unconnected-(PINS5-Pad4)") (class "Default")
      (node (ref "PINS5") (pin "4") (pinfunction "4_4") (pintype "passive"))
    )
    (net (code "93") (name "unconnected-(PINS5-Pad5)") (class "Default")
      (node (ref "PINS5") (pin "5") (pinfunction "5_5") (pintype "passive"))
    )
    (net (code "94") (name "unconnected-(PINS5-Pad6)") (class "Default")
      (node (ref "PINS5") (pin "6") (pinfunction "6_6") (pintype "passive"))
    )
    (net (code "95") (name "unconnected-(PINS5-Pad7)") (class "Default")
      (node (ref "PINS5") (pin "7") (pinfunction "7_7") (pintype "passive"))
    )
    (net (code "96") (name "unconnected-(PINS7-Pad1)") (class "Default")
      (node (ref "PINS7") (pin "1") (pinfunction "1_1") (pintype "passive"))
    )
    (net (code "97") (name "unconnected-(PINS7-Pad2)") (class "Default")
      (node (ref "PINS7") (pin "2") (pinfunction "2_2") (pintype "passive"))
    )
    (net (code "98") (name "unconnected-(PINS7-Pad3)") (class "Default")
      (node (ref "PINS7") (pin "3") (pinfunction "3_3") (pintype "passive"))
    )
    (net (code "99") (name "unconnected-(PINS7-Pad4)") (class "Default")
      (node (ref "PINS7") (pin "4") (pinfunction "4_4") (pintype "passive"))
    )
    (net (code "100") (name "unconnected-(PINS7-Pad5)") (class "Default")
      (node (ref "PINS7") (pin "5") (pinfunction "5_5") (pintype "passive"))
    )
    (net (code "101") (name "unconnected-(PINS7-Pad6)") (class "Default")
      (node (ref "PINS7") (pin "6") (pinfunction "6_6") (pintype "passive"))
    )
    (net (code "102") (name "unconnected-(PINS7-Pad7)") (class "Default")
      (node (ref "PINS7") (pin "7") (pinfunction "7_7") (pintype "passive"))
    )
    (net (code "103") (name "unconnected-(PINS8-Pad1)") (class "Default")
      (node (ref "PINS8") (pin "1") (pinfunction "1_1") (pintype "passive"))
    )
    (net (code "104") (name "unconnected-(PINS8-Pad2)") (class "Default")
      (node (ref "PINS8") (pin "2") (pinfunction "2_2") (pintype "passive"))
    )
    (net (code "105") (name "unconnected-(PINS8-Pad3)") (class "Default")
      (node (ref "PINS8") (pin "3") (pinfunction "3_3") (pintype "passive"))
    )
    (net (code "106") (name "unconnected-(PINS8-Pad4)") (class "Default")
      (node (ref "PINS8") (pin "4") (pinfunction "4_4") (pintype "passive"))
    )
    (net (code "107") (name "unconnected-(PINS8-Pad5)") (class "Default")
      (node (ref "PINS8") (pin "5") (pinfunction "5_5") (pintype "passive"))
    )
    (net (code "108") (name "unconnected-(PINS8-Pad6)") (class "Default")
      (node (ref "PINS8") (pin "6") (pinfunction "6_6") (pintype "passive"))
    )
    (net (code "109") (name "unconnected-(PINS8-Pad7)") (class "Default")
      (node (ref "PINS8") (pin "7") (pinfunction "7_7") (pintype "passive"))
    )
    (net (code "110") (name "unconnected-(RGB1B-Pad2)") (class "Default")
      (node (ref "RGB1B") (pin "2") (pinfunction "2_2") (pintype "passive"))
    )
    (net (code "111") (name "unconnected-(RGB2B-Pad2)") (class "Default")
      (node (ref "RGB2B") (pin "2") (pinfunction "2_2") (pintype "passive"))
    )
    (net (code "112") (name "unconnected-(RGB3B-Pad2)") (class "Default")
      (node (ref "RGB3B") (pin "2") (pinfunction "2_2") (pintype "passive"))
    )
    (net (code "113") (name "unconnected-(RGB4B-Pad2)") (class "Default")
      (node (ref "RGB4B") (pin "2") (pinfunction "2_2") (pintype "passive"))
    )
    (net (code "114") (name "unconnected-(SV11-Pad1)") (class "Default")
      (node (ref "SV11") (pin "1") (pinfunction "1_1") (pintype "passive"))
    )
    (net (code "115") (name "unconnected-(U$3-7-PadMCLR)") (class "Default")
      (node (ref "U$3") (pin "MCLR") (pinfunction "7_MCLR") (pintype "passive"))
    )
    (net (code "116") (name "unconnected-(U$4-PadF2)") (class "Default")
      (node (ref "U$4") (pin "F2") (pinfunction "F2_F2") (pintype "passive"))
    )
    (net (code "117") (name "unconnected-(U$4-PadF3)") (class "Default")
      (node (ref "U$4") (pin "F3") (pinfunction "F3_F3") (pintype "passive"))
    )
  )
)
